# CocoMake7_USB-stick_SMD_v01_stahl.net
KiCad netlist of a schematic drawn in EAGLE
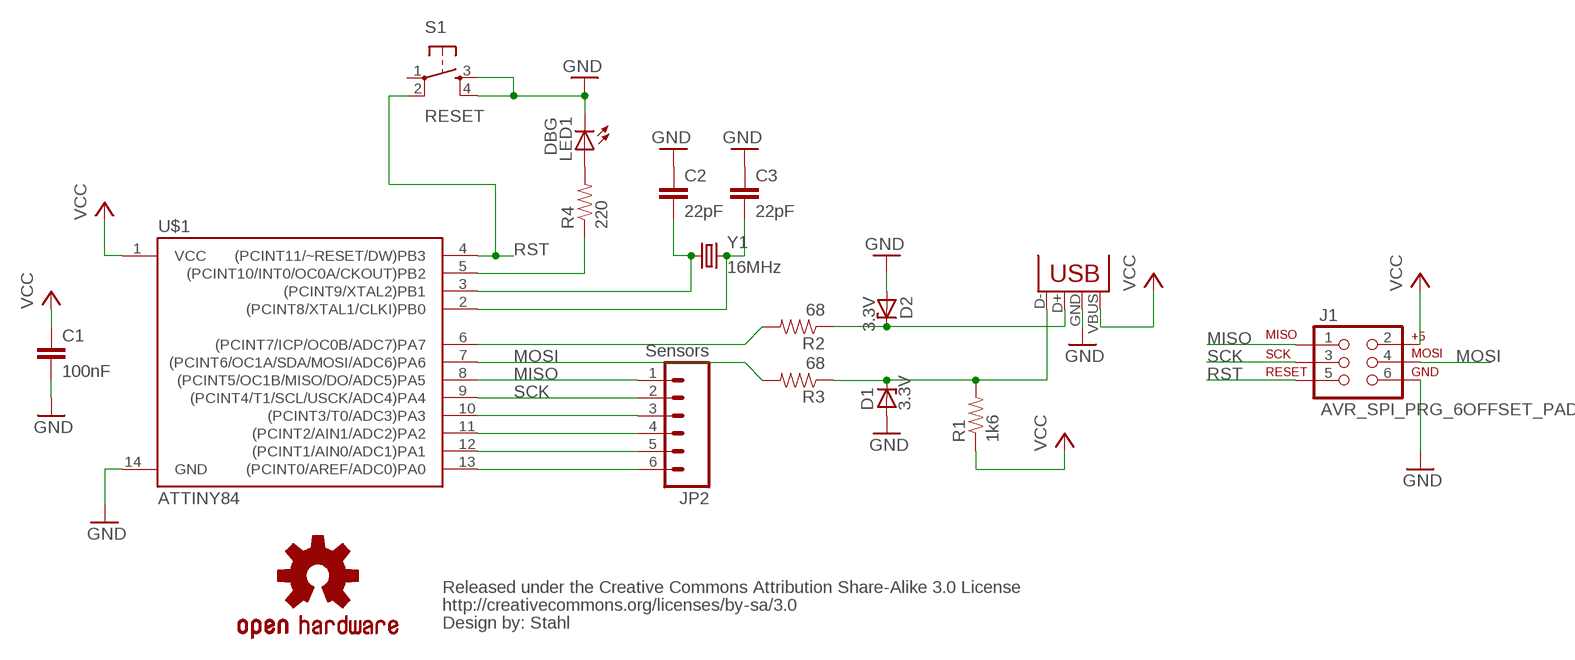
[diagram p0: schematic, sheet 1]

(export (version "E")
  (design (tool "Eeschema 10.0.6"))
  (components
    (comp (ref "C1")
      (value "100nF")
      (footprint "eagle-import:1206")
      (libsource (lib "eagle-import") (part "CAP1206"))
    )
    (comp (ref "C2")
      (value "22pF")
      (footprint "eagle-import:1206")
      (libsource (lib "eagle-import") (part "CAP1206"))
    )
    (comp (ref "C3")
      (value "22pF")
      (footprint "eagle-import:1206")
      (libsource (lib "eagle-import") (part "CAP1206"))
    )
    (comp (ref "CC_TEXT1")
      (value "CREATIVE_COMMONS")
      (footprint "eagle-import:CREATIVE_COMMONS")
      (libsource (lib "eagle-import") (part "CREATIVE_COMMONS"))
    )
    (comp (ref "D1")
      (value "3.3V")
      (footprint "eagle-import:SOD80C")
      (libsource (lib "eagle-import") (part "ZENER-DIODESOD80C"))
    )
    (comp (ref "D2")
      (value "3.3V")
      (footprint "eagle-import:SOD80C")
      (libsource (lib "eagle-import") (part "ZENER-DIODESOD80C"))
    )
    (comp (ref "J1")
      (value "AVR_SPI_PRG_6OFFSET_PADS")
      (footprint "eagle-import:2X3_OFFSET")
      (libsource (lib "eagle-import") (part "AVR_SPI_PRG_6OFFSET_PADS"))
    )
    (comp (ref "JP1")
      (value "USB-A-H")
      (footprint "eagle-import:USB-A-H")
      (libsource (lib "eagle-import") (part "USB-A-H"))
    )
    (comp (ref "JP2")
      (value "Sensors")
      (footprint "eagle-import:1X06_LONGPADS")
      (libsource (lib "eagle-import") (part "M06LONGPADS"))
    )
    (comp (ref "LED1")
      (value "DBG")
      (footprint "eagle-import:LED-1206")
      (libsource (lib "eagle-import") (part "LED1206"))
    )
    (comp (ref "LOGO1")
      (value "OSHW-LOGOS")
      (footprint "eagle-import:OSHW-LOGO-S")
      (libsource (lib "eagle-import") (part "OSHW-LOGOS"))
    )
    (comp (ref "R1")
      (value "1k6")
      (footprint "eagle-import:1206")
      (libsource (lib "eagle-import") (part "RESISTOR1206"))
    )
    (comp (ref "R2")
      (value "68")
      (footprint "eagle-import:1206")
      (libsource (lib "eagle-import") (part "RESISTOR1206"))
    )
    (comp (ref "R3")
      (value "68")
      (footprint "eagle-import:1206")
      (libsource (lib "eagle-import") (part "RESISTOR1206"))
    )
    (comp (ref "R4")
      (value "220")
      (footprint "eagle-import:1206")
      (libsource (lib "eagle-import") (part "RESISTOR1206"))
    )
    (comp (ref "S1")
      (value "RESET")
      (footprint "eagle-import:TACTILE_SWITCH_SMD")
      (libsource (lib "eagle-import") (part "TAC_SWITCHSMD"))
    )
    (comp (ref "U$1")
      (value "ATTINY84")
      (footprint "eagle-import:SO14")
      (libsource (lib "eagle-import") (part "ATTINY84"))
    )
    (comp (ref "Y1")
      (value "16MHz")
      (footprint "eagle-import:HC49UP")
      (libsource (lib "eagle-import") (part "CRYSTALSMD"))
    )
  )
  (nets
    (net (code "1") (name "/MISO") (class "Default")
      (node (ref "J1") (pin "1") (pinfunction "1_1") (pintype "passive"))
      (node (ref "JP2") (pin "1") (pinfunction "1_1") (pintype "passive"))
      (node (ref "U$1") (pin "8") (pinfunction "(PCINT5/OC1B/MISO/DO/ADC5)PA5_8") (pintype "bidirectional"))
    )
    (net (code "2") (name "/MOSI") (class "Default")
      (node (ref "J1") (pin "4") (pinfunction "4_4") (pintype "passive"))
      (node (ref "R3") (pin "2") (pinfunction "2_2") (pintype "passive"))
      (node (ref "U$1") (pin "7") (pinfunction "(PCINT6/OC1A/SDA/MOSI/ADC6)PA6_7") (pintype "bidirectional"))
    )
    (net (code "3") (name "/RST") (class "Default")
      (node (ref "J1") (pin "5") (pinfunction "5_5") (pintype "passive"))
      (node (ref "S1") (pin "2") (pinfunction "2_2") (pintype "passive"))
      (node (ref "U$1") (pin "4") (pinfunction "(PCINT11/~{RESET/DW})PB3_4") (pintype "bidirectional"))
    )
    (net (code "4") (name "/SCK") (class "Default")
      (node (ref "J1") (pin "3") (pinfunction "3_3") (pintype "passive"))
      (node (ref "JP2") (pin "2") (pinfunction "2_2") (pintype "passive"))
      (node (ref "U$1") (pin "9") (pinfunction "(PCINT4/T1/SCL/USCK/ADC4)PA4_9") (pintype "bidirectional"))
    )
    (net (code "5") (name "GND") (class "Default")
      (node (ref "C1") (pin "2") (pinfunction "2_2") (pintype "passive"))
      (node (ref "C2") (pin "1") (pinfunction "1_1") (pintype "passive"))
      (node (ref "C3") (pin "1") (pinfunction "1_1") (pintype "passive"))
      (node (ref "D1") (pin "A") (pinfunction "A_A") (pintype "passive"))
      (node (ref "D2") (pin "A") (pinfunction "A_A") (pintype "passive"))
      (node (ref "J1") (pin "6") (pinfunction "6_6") (pintype "passive"))
      (node (ref "JP1") (pin "GND") (pinfunction "VBUS_GND") (pintype "bidirectional"))
      (node (ref "LED1") (pin "C") (pinfunction "C_C") (pintype "passive"))
      (node (ref "S1") (pin "3") (pinfunction "3_3") (pintype "passive"))
      (node (ref "S1") (pin "4") (pinfunction "4_4") (pintype "passive"))
      (node (ref "U$1") (pin "14") (pinfunction "GND_14") (pintype "bidirectional"))
    )
    (net (code "6") (name "Net-(JP1-D+)") (class "Default")
      (node (ref "D1") (pin "C") (pinfunction "C_C") (pintype "passive"))
      (node (ref "JP1") (pin "D-") (pinfunction "D+_D-") (pintype "bidirectional"))
      (node (ref "R1") (pin "2") (pinfunction "2_2") (pintype "passive"))
      (node (ref "R3") (pin "1") (pinfunction "1_1") (pintype "passive"))
    )
    (net (code "7") (name "Net-(JP1-D-)") (class "Default")
      (node (ref "D2") (pin "C") (pinfunction "C_C") (pintype "passive"))
      (node (ref "JP1") (pin "D+") (pinfunction "D-_D+") (pintype "bidirectional"))
      (node (ref "R2") (pin "1") (pinfunction "1_1") (pintype "passive"))
    )
    (net (code "8") (name "Net-(LED1-PadA)") (class "Default")
      (node (ref "LED1") (pin "A") (pinfunction "A_A") (pintype "passive"))
      (node (ref "R4") (pin "2") (pinfunction "2_2") (pintype "passive"))
    )
    (net (code "9") (name "Net-(U$1-(PCINT0{slash}AREF{slash}ADC0)PA0)") (class "Default")
      (node (ref "JP2") (pin "6") (pinfunction "6_6") (pintype "passive"))
      (node (ref "U$1") (pin "13") (pinfunction "(PCINT0/AREF/ADC0)PA0_13") (pintype "bidirectional"))
    )
    (net (code "10") (name "Net-(U$1-(PCINT1{slash}AIN0{slash}ADC1)PA1)") (class "Default")
      (node (ref "JP2") (pin "5") (pinfunction "5_5") (pintype "passive"))
      (node (ref "U$1") (pin "12") (pinfunction "(PCINT1/AIN0/ADC1)PA1_12") (pintype "bidirectional"))
    )
    (net (code "11") (name "Net-(U$1-(PCINT2{slash}AIN1{slash}ADC2)PA2)") (class "Default")
      (node (ref "JP2") (pin "4") (pinfunction "4_4") (pintype "passive"))
      (node (ref "U$1") (pin "11") (pinfunction "(PCINT2/AIN1/ADC2)PA2_11") (pintype "bidirectional"))
    )
    (net (code "12") (name "Net-(U$1-(PCINT3{slash}T0{slash}ADC3)PA3)") (class "Default")
      (node (ref "JP2") (pin "3") (pinfunction "3_3") (pintype "passive"))
      (node (ref "U$1") (pin "10") (pinfunction "(PCINT3/T0/ADC3)PA3_10") (pintype "bidirectional"))
    )
    (net (code "13") (name "Net-(U$1-(PCINT7{slash}ICP{slash}OC0B{slash}ADC7)PA7)") (class "Default")
      (node (ref "R2") (pin "2") (pinfunction "2_2") (pintype "passive"))
      (node (ref "U$1") (pin "6") (pinfunction "(PCINT7/ICP/OC0B/ADC7)PA7_6") (pintype "bidirectional"))
    )
    (net (code "14") (name "Net-(U$1-(PCINT8{slash}XTAL1{slash}CLKI)PB0)") (class "Default")
      (node (ref "C3") (pin "2") (pinfunction "2_2") (pintype "passive"))
      (node (ref "U$1") (pin "2") (pinfunction "(PCINT8/XTAL1/CLKI)PB0_2") (pintype "bidirectional"))
      (node (ref "Y1") (pin "2") (pinfunction "2_2") (pintype "passive"))
    )
    (net (code "15") (name "Net-(U$1-(PCINT9{slash}XTAL2)PB1)") (class "Default")
      (node (ref "C2") (pin "2") (pinfunction "2_2") (pintype "passive"))
      (node (ref "U$1") (pin "3") (pinfunction "(PCINT9/XTAL2)PB1_3") (pintype "bidirectional"))
      (node (ref "Y1") (pin "1") (pinfunction "1_1") (pintype "passive"))
    )
    (net (code "16") (name "Net-(U$1-(PCINT10{slash}INT0{slash}OC0A{slash}CKOUT)PB2)") (class "Default")
      (node (ref "R4") (pin "1") (pinfunction "1_1") (pintype "passive"))
      (node (ref "U$1") (pin "5") (pinfunction "(PCINT10/INT0/OC0A/CKOUT)PB2_5") (pintype "bidirectional"))
    )
    (net (code "17") (name "VCC") (class "Default")
      (node (ref "C1") (pin "1") (pinfunction "1_1") (pintype "passive"))
      (node (ref "J1") (pin "2") (pinfunction "2_2") (pintype "passive"))
      (node (ref "JP1") (pin "VBUS") (pinfunction "GND_VBUS") (pintype "bidirectional"))
      (node (ref "R1") (pin "1") (pinfunction "1_1") (pintype "passive"))
      (node (ref "U$1") (pin "1") (pinfunction "VCC_1") (pintype "bidirectional"))
    )
    (net (code "18") (name "unconnected-(S1-Pad1)") (class "Default")
      (node (ref "S1") (pin "1") (pinfunction "1_1") (pintype "passive"))
    )
  )
)
